# TipWiring.net
KiCad netlist of a schematic drawn in Altium Designer
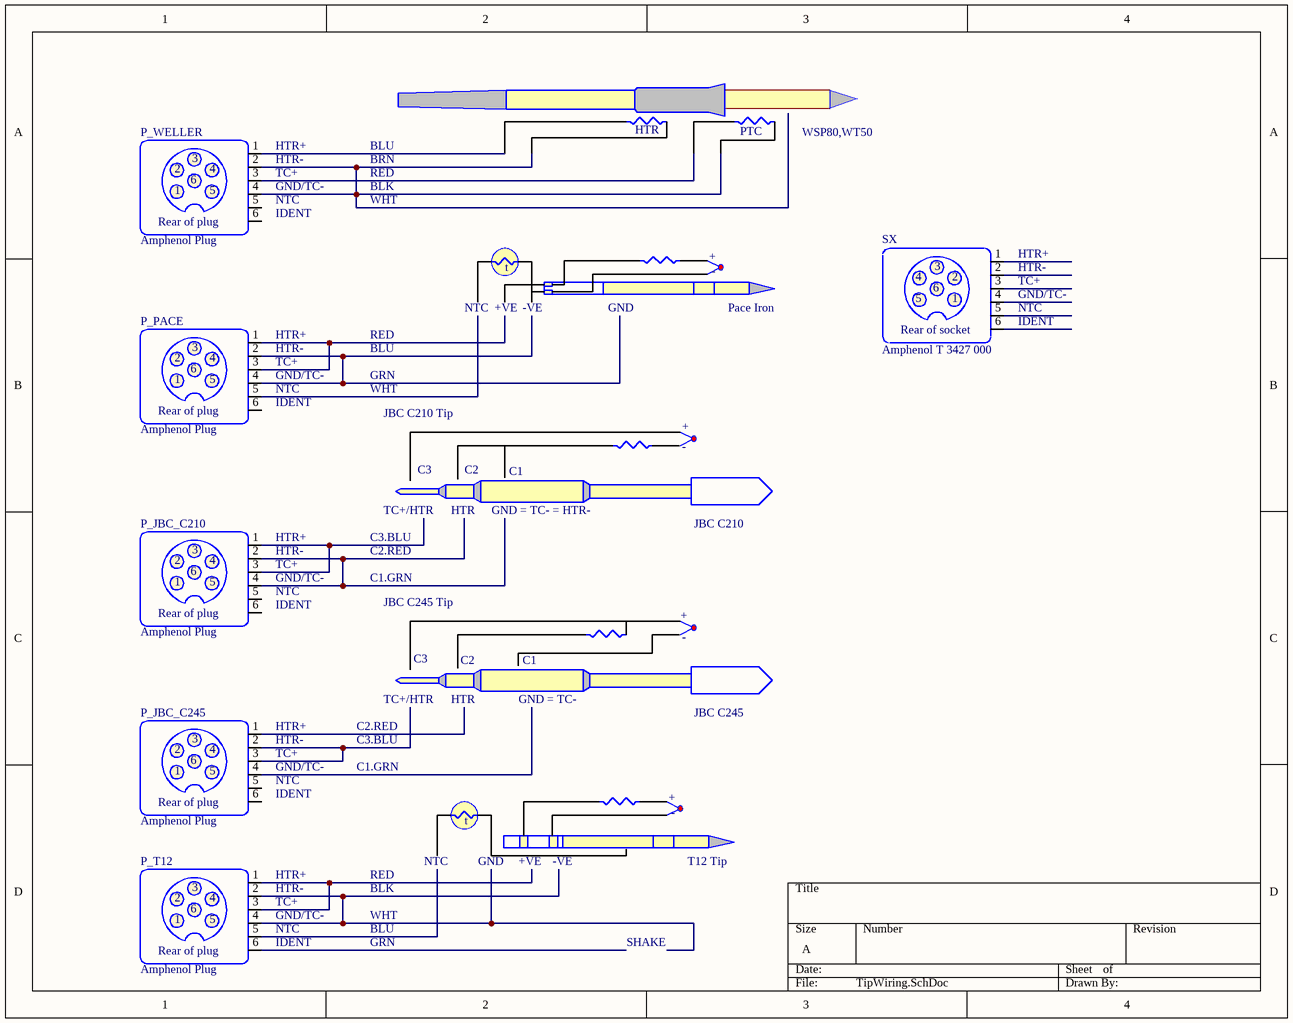
[diagram p0: TipWiring.SchDoc]

(export (version "E")
  (design (tool "Eeschema 10.0.6"))
  (components
    (comp (ref "JBC C210 Tip") (value "JBC C210") (libsource (lib "MySchLib") (part "JBC C210")))
    (comp (ref "JBC C245 Tip") (value "JBC C245") (libsource (lib "MySchLib") (part "JBC C245")))
    (comp (ref "Pace Iron") (value "Pace") (libsource (lib "MySchLib") (part "Pace")))
    (comp (ref "P_JBC_C210")
      (value "Amphenol Plug")
      (description "Circular Connector, C091B Series, Panel Mount Receptacle, 6 Contacts, Solder Socket, Metal Body")
      (libsource (lib "MySchLib") (part "Amphenol Plug"))
    )
    (comp (ref "P_JBC_C245")
      (value "Amphenol Plug")
      (description "Circular Connector, C091B Series, Panel Mount Receptacle, 6 Contacts, Solder Socket, Metal Body")
      (libsource (lib "MySchLib") (part "Amphenol Plug"))
    )
    (comp (ref "P_PACE")
      (value "Amphenol Plug")
      (description "Circular Connector, C091B Series, Panel Mount Receptacle, 6 Contacts, Solder Socket, Metal Body")
      (libsource (lib "MySchLib") (part "Amphenol Plug"))
    )
    (comp (ref "P_T12")
      (value "Amphenol Plug")
      (description "Circular Connector, C091B Series, Panel Mount Receptacle, 6 Contacts, Solder Socket, Metal Body")
      (libsource (lib "MySchLib") (part "Amphenol Plug"))
    )
    (comp (ref "P_WELLER")
      (value "Amphenol Plug")
      (description "Circular Connector, C091B Series, Panel Mount Receptacle, 6 Contacts, Solder Socket, Metal Body")
      (libsource (lib "MySchLib") (part "Amphenol Plug"))
    )
    (comp (ref "SX")
      (value "Amphenol T 3427 000")
      (description "Circular Connector, C091B Series, Panel Mount Receptacle, 6 Contacts, Solder Socket, Metal Body")
      (libsource (lib "MySchLib") (part "Amphenol T 3427 000"))
    )
    (comp (ref "T12 Tip") (value "T12 Tip") (libsource (lib "MySchLib") (part "T12 Tip")))
    (comp (ref "WSP80,WT50") (value "WELLER WSP80") (libsource (lib "MySchLib") (part "WELLER WSP80")))
  )
  (nets
    (net (code "1") (name "Net-(P_JBC_C210-Pad1)") (class "Default")
      (node (ref "P_JBC_C210") (pin "1") (pinfunction "1_1") (pintype "passive"))
      (node (ref "P_JBC_C210") (pin "3") (pinfunction "3_3") (pintype "passive"))
    )
    (net (code "2") (name "Net-(P_JBC_C210-Pad2)") (class "Default")
      (node (ref "P_JBC_C210") (pin "2") (pinfunction "2_2") (pintype "passive"))
      (node (ref "P_JBC_C210") (pin "4") (pinfunction "4_4") (pintype "passive"))
    )
    (net (code "3") (name "Net-(P_JBC_C245-Pad2)") (class "Default")
      (node (ref "P_JBC_C245") (pin "2") (pinfunction "2_2") (pintype "passive"))
      (node (ref "P_JBC_C245") (pin "3") (pinfunction "3_3") (pintype "passive"))
    )
    (net (code "4") (name "Net-(P_PACE-Pad1)") (class "Default")
      (node (ref "P_PACE") (pin "1") (pinfunction "1_1") (pintype "passive"))
      (node (ref "P_PACE") (pin "3") (pinfunction "3_3") (pintype "passive"))
    )
    (net (code "5") (name "Net-(P_PACE-Pad2)") (class "Default")
      (node (ref "P_PACE") (pin "2") (pinfunction "2_2") (pintype "passive"))
      (node (ref "P_PACE") (pin "4") (pinfunction "4_4") (pintype "passive"))
    )
    (net (code "6") (name "Net-(P_T12-Pad1)") (class "Default")
      (node (ref "P_T12") (pin "1") (pinfunction "1_1") (pintype "passive"))
      (node (ref "P_T12") (pin "3") (pinfunction "3_3") (pintype "passive"))
    )
    (net (code "7") (name "Net-(P_T12-Pad2)") (class "Default")
      (node (ref "P_T12") (pin "2") (pinfunction "2_2") (pintype "passive"))
      (node (ref "P_T12") (pin "4") (pinfunction "4_4") (pintype "passive"))
    )
    (net (code "8") (name "Net-(P_WELLER-Pad2)") (class "Default")
      (node (ref "P_WELLER") (pin "2") (pinfunction "2_2") (pintype "passive"))
      (node (ref "P_WELLER") (pin "4") (pinfunction "4_4") (pintype "passive"))
    )
    (net (code "9") (name "unconnected-(P_JBC_C210-Pad5)") (class "Default")
      (node (ref "P_JBC_C210") (pin "5") (pinfunction "5_5") (pintype "passive"))
    )
    (net (code "10") (name "unconnected-(P_JBC_C210-Pad6)") (class "Default")
      (node (ref "P_JBC_C210") (pin "6") (pinfunction "6_6") (pintype "passive"))
    )
    (net (code "11") (name "unconnected-(P_JBC_C245-Pad1)") (class "Default")
      (node (ref "P_JBC_C245") (pin "1") (pinfunction "1_1") (pintype "passive"))
    )
    (net (code "12") (name "unconnected-(P_JBC_C245-Pad4)") (class "Default")
      (node (ref "P_JBC_C245") (pin "4") (pinfunction "4_4") (pintype "passive"))
    )
    (net (code "13") (name "unconnected-(P_JBC_C245-Pad5)") (class "Default")
      (node (ref "P_JBC_C245") (pin "5") (pinfunction "5_5") (pintype "passive"))
    )
    (net (code "14") (name "unconnected-(P_JBC_C245-Pad6)") (class "Default")
      (node (ref "P_JBC_C245") (pin "6") (pinfunction "6_6") (pintype "passive"))
    )
    (net (code "15") (name "unconnected-(P_PACE-Pad5)") (class "Default")
      (node (ref "P_PACE") (pin "5") (pinfunction "5_5") (pintype "passive"))
    )
    (net (code "16") (name "unconnected-(P_PACE-Pad6)") (class "Default")
      (node (ref "P_PACE") (pin "6") (pinfunction "6_6") (pintype "passive"))
    )
    (net (code "17") (name "unconnected-(P_T12-Pad5)") (class "Default")
      (node (ref "P_T12") (pin "5") (pinfunction "5_5") (pintype "passive"))
    )
    (net (code "18") (name "unconnected-(P_T12-Pad6)") (class "Default")
      (node (ref "P_T12") (pin "6") (pinfunction "6_6") (pintype "passive"))
    )
    (net (code "19") (name "unconnected-(P_WELLER-Pad1)") (class "Default")
      (node (ref "P_WELLER") (pin "1") (pinfunction "1_1") (pintype "passive"))
    )
    (net (code "20") (name "unconnected-(P_WELLER-Pad3)") (class "Default")
      (node (ref "P_WELLER") (pin "3") (pinfunction "3_3") (pintype "passive"))
    )
    (net (code "21") (name "unconnected-(P_WELLER-Pad5)") (class "Default")
      (node (ref "P_WELLER") (pin "5") (pinfunction "5_5") (pintype "passive"))
    )
    (net (code "22") (name "unconnected-(P_WELLER-Pad6)") (class "Default")
      (node (ref "P_WELLER") (pin "6") (pinfunction "6_6") (pintype "passive"))
    )
    (net (code "23") (name "unconnected-(SX-Pad1)") (class "Default")
      (node (ref "SX") (pin "1") (pinfunction "1_1") (pintype "passive"))
    )
    (net (code "24") (name "unconnected-(SX-Pad2)") (class "Default")
      (node (ref "SX") (pin "2") (pinfunction "2_2") (pintype "passive"))
    )
    (net (code "25") (name "unconnected-(SX-Pad3)") (class "Default")
      (node (ref "SX") (pin "3") (pinfunction "3_3") (pintype "passive"))
    )
    (net (code "26") (name "unconnected-(SX-Pad4)") (class "Default")
      (node (ref "SX") (pin "4") (pinfunction "4_4") (pintype "passive"))
    )
    (net (code "27") (name "unconnected-(SX-Pad5)") (class "Default")
      (node (ref "SX") (pin "5") (pinfunction "5_5") (pintype "passive"))
    )
    (net (code "28") (name "unconnected-(SX-Pad6)") (class "Default")
      (node (ref "SX") (pin "6") (pinfunction "6_6") (pintype "passive"))
    )
  )
)
